# lab1_shkabara_usb_rs232.net
KiCad netlist of a schematic drawn in Altium Designer
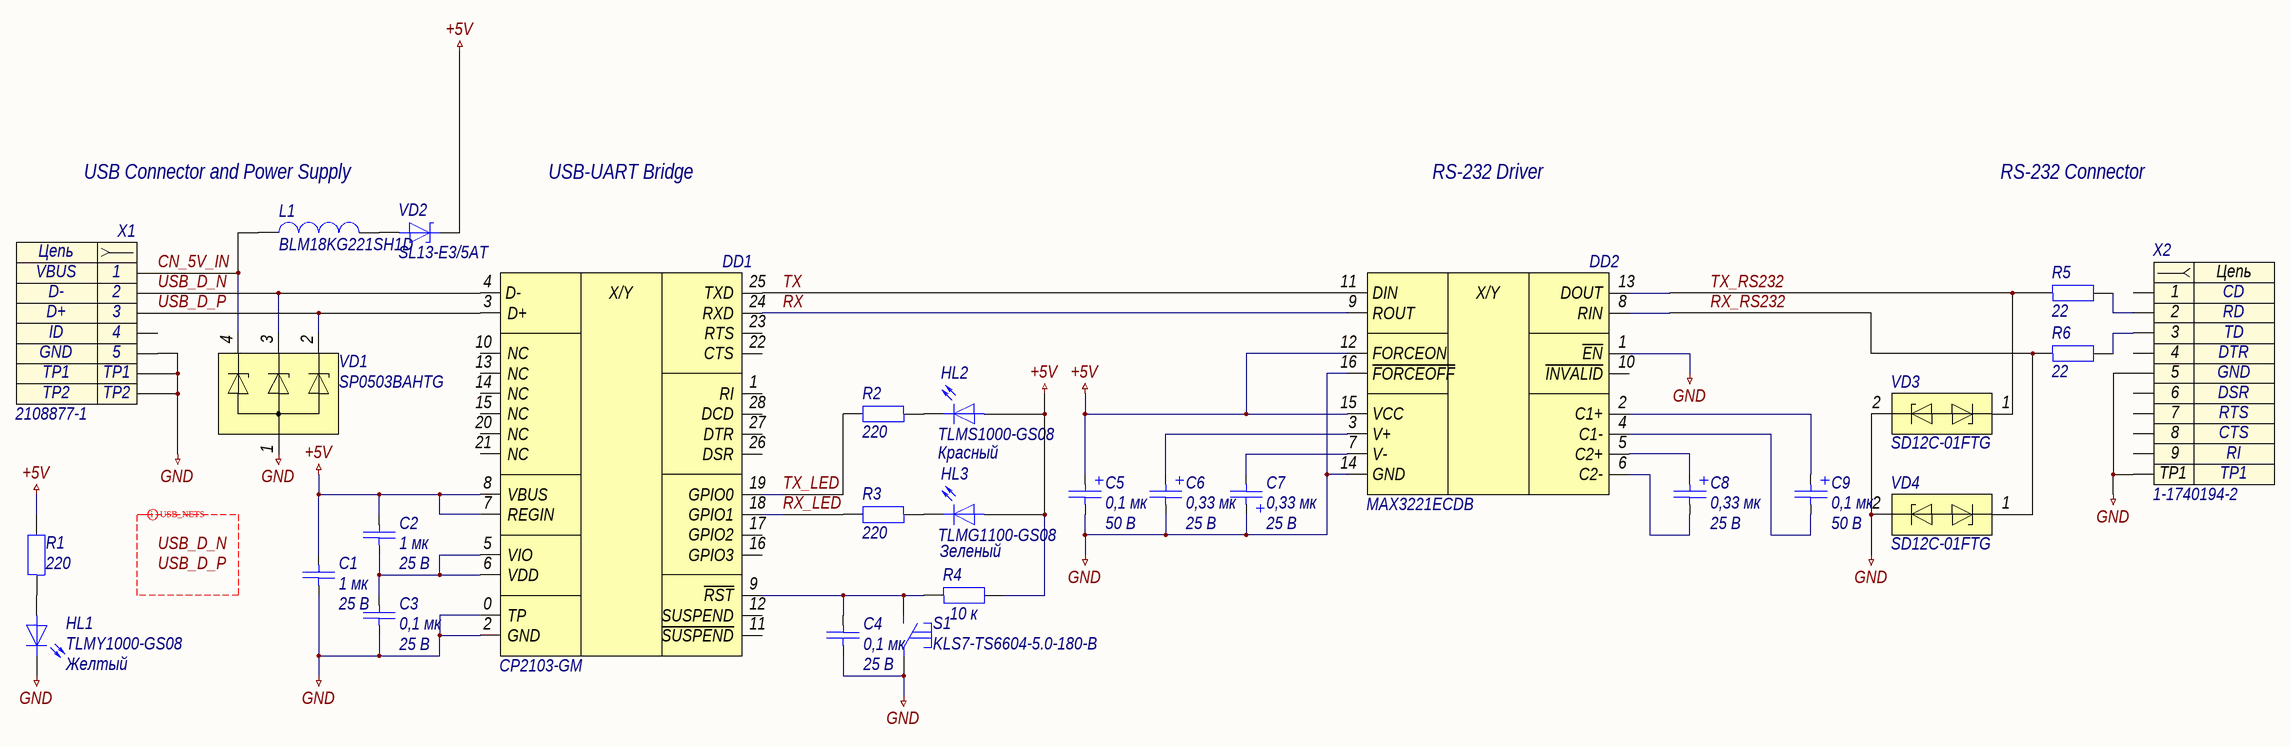
[diagram p0: lab1_shkabara_usb_rs232.SchDoc]

(export (version "E")
  (design (tool "Eeschema 10.0.6"))
  (components
    (comp (ref "C1")
      (value "1 мк")
      (footprint "C0603")
      (description "=Описание")
      (fields (field (name "НАПРЯЖЕНИЕ") "25 В"))
      (libsource (lib "Database_Students") (part "CAPACITOR-NONPOLAR"))
    )
    (comp (ref "C2")
      (value "1 мк")
      (footprint "C0603")
      (description "=Описание")
      (fields (field (name "НАПРЯЖЕНИЕ") "25 В"))
      (libsource (lib "Database_Students") (part "CAPACITOR-NONPOLAR"))
    )
    (comp (ref "C3")
      (value "0,1 мк")
      (footprint "C0603")
      (description "=Описание")
      (fields (field (name "НАПРЯЖЕНИЕ") "25 В"))
      (libsource (lib "Database_Students") (part "CAPACITOR-NONPOLAR"))
    )
    (comp (ref "C4")
      (value "0,1 мк")
      (footprint "C0603")
      (description "=Описание")
      (fields (field (name "НАПРЯЖЕНИЕ") "25 В"))
      (libsource (lib "Database_Students") (part "CAPACITOR-NONPOLAR"))
    )
    (comp (ref "C5")
      (value "0,1 мк")
      (footprint "C3216-18")
      (description "=Описание")
      (fields (field (name "НАПРЯЖЕНИЕ") "50 В"))
      (libsource (lib "Database_Students") (part "CAPACITOR-POLAR"))
    )
    (comp (ref "C6")
      (value "0,33 мк")
      (footprint "C3216-18")
      (description "=Описание")
      (fields (field (name "НАПРЯЖЕНИЕ") "25 В"))
      (libsource (lib "Database_Students") (part "CAPACITOR-POLAR"))
    )
    (comp (ref "C7")
      (value "0,33 мк")
      (footprint "C3216-18")
      (description "=Описание")
      (fields (field (name "НАПРЯЖЕНИЕ") "25 В"))
      (libsource (lib "Database_Students") (part "CAPACITOR-POLAR"))
    )
    (comp (ref "C8")
      (value "0,33 мк")
      (footprint "C3216-18")
      (description "=Описание")
      (fields (field (name "НАПРЯЖЕНИЕ") "25 В"))
      (libsource (lib "Database_Students") (part "CAPACITOR-POLAR"))
    )
    (comp (ref "C9")
      (value "0,1 мк")
      (footprint "C3216-18")
      (description "=Описание")
      (fields (field (name "НАПРЯЖЕНИЕ") "50 В"))
      (libsource (lib "Database_Students") (part "CAPACITOR-POLAR"))
    )
    (comp (ref "DD1")
      (value "CP2103-GM")
      (footprint "QFN-28-500X500X90")
      (description "=Описание")
      (libsource (lib "Database_Students") (part "CP2103-GM"))
    )
    (comp (ref "DD2")
      (value "MAX3221ECDB")
      (footprint "SSOP-16-620X530X195")
      (description "=Описание")
      (libsource (lib "Database_Students") (part "MAX3221ECDB"))
    )
    (comp (ref "HL1")
      (value "TLMY1000-GS08")
      (footprint "HL0603")
      (description "=Описание")
      (fields (field (name "ЦВЕТ") "Желтый"))
      (libsource (lib "Database_Students") (part "LED-COMMON"))
    )
    (comp (ref "HL2")
      (value "TLMS1000-GS08")
      (footprint "HL0603")
      (description "=Описание")
      (fields (field (name "ЦВЕТ") "Красный"))
      (libsource (lib "Database_Students") (part "LED-COMMON"))
    )
    (comp (ref "HL3")
      (value "TLMG1100-GS08")
      (footprint "HL0603")
      (description "=Описание")
      (fields (field (name "ЦВЕТ") "Зеленый"))
      (libsource (lib "Database_Students") (part "LED-COMMON"))
    )
    (comp (ref "L1")
      (value "BLM18KG221SH1D")
      (footprint "BLM-2-0603")
      (description "=Описание")
      (libsource (lib "Database_Students") (part "FERRITE-BEAD"))
    )
    (comp (ref "R1")
      (value "220")
      (footprint "R0603")
      (description "=Описание")
      (libsource (lib "Database_Students") (part "RESISTOR-COMMON"))
    )
    (comp (ref "R2")
      (value "220")
      (footprint "R0603")
      (description "=Описание")
      (libsource (lib "Database_Students") (part "RESISTOR-COMMON"))
    )
    (comp (ref "R3")
      (value "220")
      (footprint "R0603")
      (description "=Описание")
      (libsource (lib "Database_Students") (part "RESISTOR-COMMON"))
    )
    (comp (ref "R4")
      (value "10 к")
      (footprint "R0603")
      (description "=Описание")
      (libsource (lib "Database_Students") (part "RESISTOR-COMMON"))
    )
    (comp (ref "R5")
      (value "22")
      (footprint "R0603")
      (description "=Описание")
      (libsource (lib "Database_Students") (part "RESISTOR-COMMON"))
    )
    (comp (ref "R6")
      (value "22")
      (footprint "R0603")
      (description "=Описание")
      (libsource (lib "Database_Students") (part "RESISTOR-COMMON"))
    )
    (comp (ref "S1")
      (value "KLS7-TS6604-5.0-180-B")
      (footprint "KLS7-TS6604-5.0-180-B")
      (description "=Описание")
      (libsource (lib "Database_Students") (part "BUTTON"))
    )
    (comp (ref "VD1")
      (value "SP0503BAHTG")
      (footprint "SOT-143-4")
      (description "=Описание")
      (libsource (lib "Database_Students") (part "SP0503BAHTG"))
    )
    (comp (ref "VD2")
      (value "SL13-E3/5AT")
      (footprint "DO-214AC")
      (description "=Описание")
      (libsource (lib "Database_Students") (part "DIODE-SCHOTTKY"))
    )
    (comp (ref "VD3")
      (value "SD12C-01FTG")
      (footprint "SOD-323")
      (description "=Описание")
      (libsource (lib "Database_Students") (part "ZENER-BI-DIRECTIONAL"))
    )
    (comp (ref "VD4")
      (value "SD12C-01FTG")
      (footprint "SOD-323")
      (description "=Описание")
      (libsource (lib "Database_Students") (part "ZENER-BI-DIRECTIONAL"))
    )
    (comp (ref "X1")
      (value "2108877-1")
      (footprint "2108877-1")
      (libsource (lib "2108877-1_micro_usb-b") (part "2108877-1_micro_usb-b"))
    )
    (comp (ref "X2")
      (value "1-1740194-2")
      (footprint "Other:1-1740194-2")
      (description "D-Sub 9 pin Board-to-Board")
      (libsource (lib "Other") (part "HEADER-9-TP1-SCT"))
    )
  )
  (nets
    (net (code "1") (name "+5V") (class "Default")
      (node (ref "C1") (pin "1") (pinfunction "1_1") (pintype "passive"))
      (node (ref "C2") (pin "1") (pinfunction "1_1") (pintype "passive"))
      (node (ref "C5") (pin "1") (pinfunction "1_1") (pintype "passive"))
      (node (ref "DD1") (pin "7") (pinfunction "REGIN_7") (pintype "passive"))
      (node (ref "DD1") (pin "8") (pinfunction "VBUS_8") (pintype "passive"))
      (node (ref "DD2") (pin "12") (pinfunction "FORCEON_12") (pintype "passive"))
      (node (ref "DD2") (pin "15") (pinfunction "VCC_15") (pintype "passive"))
      (node (ref "HL2") (pin "2") (pinfunction "2_2") (pintype "passive"))
      (node (ref "HL3") (pin "2") (pinfunction "2_2") (pintype "passive"))
      (node (ref "R1") (pin "2") (pinfunction "2_2") (pintype "passive"))
      (node (ref "R4") (pin "2") (pinfunction "2_2") (pintype "passive"))
      (node (ref "VD2") (pin "1") (pinfunction "1_1") (pintype "passive"))
    )
    (net (code "2") (name "/CN_5V_IN") (class "Default")
      (node (ref "L1") (pin "1") (pinfunction "1_1") (pintype "passive"))
      (node (ref "VD1") (pin "4") (pinfunction "4_4") (pintype "passive"))
      (node (ref "X1") (pin "1") (pinfunction "1_1") (pintype "passive"))
    )
    (net (code "3") (name "/RX") (class "Default")
      (node (ref "DD1") (pin "24") (pinfunction "RXD_24") (pintype "passive"))
      (node (ref "DD2") (pin "9") (pinfunction "ROUT_9") (pintype "passive"))
    )
    (net (code "4") (name "/RX_LED") (class "Default")
      (node (ref "DD1") (pin "18") (pinfunction "GPIO1_18") (pintype "passive"))
      (node (ref "R3") (pin "2") (pinfunction "2_2") (pintype "passive"))
    )
    (net (code "5") (name "/RX_RS232") (class "Default")
      (node (ref "DD2") (pin "8") (pinfunction "RIN_8") (pintype "passive"))
      (node (ref "R6") (pin "1") (pinfunction "1_1") (pintype "passive"))
      (node (ref "VD4") (pin "1") (pinfunction "1_1") (pintype "passive"))
    )
    (net (code "6") (name "/TX") (class "Default")
      (node (ref "DD1") (pin "25") (pinfunction "TXD_25") (pintype "passive"))
      (node (ref "DD2") (pin "11") (pinfunction "DIN_11") (pintype "passive"))
    )
    (net (code "7") (name "/TX_LED") (class "Default")
      (node (ref "DD1") (pin "19") (pinfunction "GPIO0_19") (pintype "passive"))
      (node (ref "R2") (pin "2") (pinfunction "2_2") (pintype "passive"))
    )
    (net (code "8") (name "/TX_RS232") (class "Default")
      (node (ref "DD2") (pin "13") (pinfunction "DOUT_13") (pintype "passive"))
      (node (ref "R5") (pin "1") (pinfunction "1_1") (pintype "passive"))
      (node (ref "VD3") (pin "1") (pinfunction "1_1") (pintype "passive"))
    )
    (net (code "9") (name "/USB_D_N") (class "Default")
      (node (ref "DD1") (pin "4") (pinfunction "D-_4") (pintype "passive"))
      (node (ref "VD1") (pin "3") (pinfunction "3_3") (pintype "passive"))
      (node (ref "X1") (pin "2") (pinfunction "2_2") (pintype "passive"))
    )
    (net (code "10") (name "/USB_D_P") (class "Default")
      (node (ref "DD1") (pin "3") (pinfunction "D+_3") (pintype "passive"))
      (node (ref "VD1") (pin "2") (pinfunction "2_2") (pintype "passive"))
      (node (ref "X1") (pin "3") (pinfunction "3_3") (pintype "passive"))
    )
    (net (code "11") (name "GND") (class "Default")
      (node (ref "C1") (pin "2") (pinfunction "2_2") (pintype "passive"))
      (node (ref "C3") (pin "2") (pinfunction "2_2") (pintype "passive"))
      (node (ref "C4") (pin "1") (pinfunction "1_1") (pintype "passive"))
      (node (ref "C5") (pin "2") (pinfunction "2_2") (pintype "passive"))
      (node (ref "C6") (pin "2") (pinfunction "2_2") (pintype "passive"))
      (node (ref "C7") (pin "1") (pinfunction "1_1") (pintype "passive"))
      (node (ref "DD1") (pin "0") (pinfunction "TP_0") (pintype "passive"))
      (node (ref "DD1") (pin "2") (pinfunction "GND_2") (pintype "passive"))
      (node (ref "DD2") (pin "1") (pinfunction "~{EN}_1") (pintype "passive"))
      (node (ref "DD2") (pin "14") (pinfunction "GND_14") (pintype "passive"))
      (node (ref "DD2") (pin "16") (pinfunction "~{FORCEOFF}_16") (pintype "passive"))
      (node (ref "HL1") (pin "1") (pinfunction "1_1") (pintype "passive"))
      (node (ref "S1") (pin "1") (pinfunction "1_1") (pintype "passive"))
      (node (ref "VD1") (pin "1") (pinfunction "1_1") (pintype "passive"))
      (node (ref "VD3") (pin "2") (pinfunction "2_2") (pintype "passive"))
      (node (ref "VD4") (pin "2") (pinfunction "2_2") (pintype "passive"))
      (node (ref "X1") (pin "5") (pinfunction "5_5") (pintype "passive"))
      (node (ref "X1") (pin "TP1") (pinfunction "TP1_TP1") (pintype "passive"))
      (node (ref "X1") (pin "TP2") (pinfunction "TP2_TP2") (pintype "passive"))
      (node (ref "X2") (pin "5") (pinfunction "5_5") (pintype "passive"))
      (node (ref "X2") (pin "TP1") (pinfunction "TP1_TP1") (pintype "passive"))
    )
    (net (code "12") (name "Net-(DD1-VDD)") (class "Default")
      (node (ref "C2") (pin "2") (pinfunction "2_2") (pintype "passive"))
      (node (ref "C3") (pin "1") (pinfunction "1_1") (pintype "passive"))
      (node (ref "DD1") (pin "5") (pinfunction "VIO_5") (pintype "passive"))
      (node (ref "DD1") (pin "6") (pinfunction "VDD_6") (pintype "passive"))
    )
    (net (code "13") (name "Net-(DD1-~{RST})") (class "Default")
      (node (ref "C4") (pin "2") (pinfunction "2_2") (pintype "passive"))
      (node (ref "DD1") (pin "9") (pinfunction "~{RST}_9") (pintype "passive"))
      (node (ref "R4") (pin "1") (pinfunction "1_1") (pintype "passive"))
      (node (ref "S1") (pin "2") (pinfunction "2_2") (pintype "passive"))
    )
    (net (code "14") (name "Net-(DD2-C1+)") (class "Default")
      (node (ref "C9") (pin "1") (pinfunction "1_1") (pintype "passive"))
      (node (ref "DD2") (pin "2") (pinfunction "C1+_2") (pintype "passive"))
    )
    (net (code "15") (name "Net-(DD2-C1-)") (class "Default")
      (node (ref "C9") (pin "2") (pinfunction "2_2") (pintype "passive"))
      (node (ref "DD2") (pin "4") (pinfunction "C1-_4") (pintype "passive"))
    )
    (net (code "16") (name "Net-(DD2-C2+)") (class "Default")
      (node (ref "C8") (pin "1") (pinfunction "1_1") (pintype "passive"))
      (node (ref "DD2") (pin "5") (pinfunction "C2+_5") (pintype "passive"))
    )
    (net (code "17") (name "Net-(DD2-C2-)") (class "Default")
      (node (ref "C8") (pin "2") (pinfunction "2_2") (pintype "passive"))
      (node (ref "DD2") (pin "6") (pinfunction "C2-_6") (pintype "passive"))
    )
    (net (code "18") (name "Net-(DD2-V+)") (class "Default")
      (node (ref "C6") (pin "1") (pinfunction "1_1") (pintype "passive"))
      (node (ref "DD2") (pin "3") (pinfunction "V+_3") (pintype "passive"))
    )
    (net (code "19") (name "Net-(DD2-V-)") (class "Default")
      (node (ref "C7") (pin "2") (pinfunction "2_2") (pintype "passive"))
      (node (ref "DD2") (pin "7") (pinfunction "V-_7") (pintype "passive"))
    )
    (net (code "20") (name "Net-(HL1-Pad2)") (class "Default")
      (node (ref "HL1") (pin "2") (pinfunction "2_2") (pintype "passive"))
      (node (ref "R1") (pin "1") (pinfunction "1_1") (pintype "passive"))
    )
    (net (code "21") (name "Net-(HL2-Pad1)") (class "Default")
      (node (ref "HL2") (pin "1") (pinfunction "1_1") (pintype "passive"))
      (node (ref "R2") (pin "1") (pinfunction "1_1") (pintype "passive"))
    )
    (net (code "22") (name "Net-(HL3-Pad1)") (class "Default")
      (node (ref "HL3") (pin "1") (pinfunction "1_1") (pintype "passive"))
      (node (ref "R3") (pin "1") (pinfunction "1_1") (pintype "passive"))
    )
    (net (code "23") (name "Net-(L1-Pad2)") (class "Default")
      (node (ref "L1") (pin "2") (pinfunction "2_2") (pintype "passive"))
      (node (ref "VD2") (pin "2") (pinfunction "2_2") (pintype "passive"))
    )
    (net (code "24") (name "Net-(R5-Pad2)") (class "Default")
      (node (ref "R5") (pin "2") (pinfunction "2_2") (pintype "passive"))
      (node (ref "X2") (pin "2") (pinfunction "2_2") (pintype "passive"))
    )
    (net (code "25") (name "Net-(R6-Pad2)") (class "Default")
      (node (ref "R6") (pin "2") (pinfunction "2_2") (pintype "passive"))
      (node (ref "X2") (pin "3") (pinfunction "3_3") (pintype "passive"))
    )
    (net (code "26") (name "unconnected-(DD1-CTS-Pad22)") (class "Default")
      (node (ref "DD1") (pin "22") (pinfunction "CTS_22") (pintype "passive"))
    )
    (net (code "27") (name "unconnected-(DD1-DCD-Pad28)") (class "Default")
      (node (ref "DD1") (pin "28") (pinfunction "DCD_28") (pintype "passive"))
    )
    (net (code "28") (name "unconnected-(DD1-DSR-Pad26)") (class "Default")
      (node (ref "DD1") (pin "26") (pinfunction "DSR_26") (pintype "passive"))
    )
    (net (code "29") (name "unconnected-(DD1-DTR-Pad27)") (class "Default")
      (node (ref "DD1") (pin "27") (pinfunction "DTR_27") (pintype "passive"))
    )
    (net (code "30") (name "unconnected-(DD1-GPIO2-Pad17)") (class "Default")
      (node (ref "DD1") (pin "17") (pinfunction "GPIO2_17") (pintype "passive"))
    )
    (net (code "31") (name "unconnected-(DD1-GPIO3-Pad16)") (class "Default")
      (node (ref "DD1") (pin "16") (pinfunction "GPIO3_16") (pintype "passive"))
    )
    (net (code "32") (name "unconnected-(DD1-NC-Pad10)") (class "Default")
      (node (ref "DD1") (pin "10") (pinfunction "NC_10") (pintype "passive"))
    )
    (net (code "33") (name "unconnected-(DD1-NC-Pad13)") (class "Default")
      (node (ref "DD1") (pin "13") (pinfunction "NC_13") (pintype "passive"))
    )
    (net (code "34") (name "unconnected-(DD1-NC-Pad14)") (class "Default")
      (node (ref "DD1") (pin "14") (pinfunction "NC_14") (pintype "passive"))
    )
    (net (code "35") (name "unconnected-(DD1-NC-Pad15)") (class "Default")
      (node (ref "DD1") (pin "15") (pinfunction "NC_15") (pintype "passive"))
    )
    (net (code "36") (name "unconnected-(DD1-NC-Pad20)") (class "Default")
      (node (ref "DD1") (pin "20") (pinfunction "NC_20") (pintype "passive"))
    )
    (net (code "37") (name "unconnected-(DD1-NC-Pad21)") (class "Default")
      (node (ref "DD1") (pin "21") (pinfunction "NC_21") (pintype "passive"))
    )
    (net (code "38") (name "unconnected-(DD1-RI-Pad1)") (class "Default")
      (node (ref "DD1") (pin "1") (pinfunction "RI_1") (pintype "passive"))
    )
    (net (code "39") (name "unconnected-(DD1-RTS-Pad23)") (class "Default")
      (node (ref "DD1") (pin "23") (pinfunction "RTS_23") (pintype "passive"))
    )
    (net (code "40") (name "unconnected-(DD1-SUSPEND-Pad12)") (class "Default")
      (node (ref "DD1") (pin "12") (pinfunction "SUSPEND_12") (pintype "passive"))
    )
    (net (code "41") (name "unconnected-(DD1-~{SUSPEND}-Pad11)") (class "Default")
      (node (ref "DD1") (pin "11") (pinfunction "~{SUSPEND}_11") (pintype "passive"))
    )
    (net (code "42") (name "unconnected-(DD2-~{INVALID}-Pad10)") (class "Default")
      (node (ref "DD2") (pin "10") (pinfunction "~{INVALID}_10") (pintype "passive"))
    )
    (net (code "43") (name "unconnected-(X1-Pad4)") (class "Default")
      (node (ref "X1") (pin "4") (pinfunction "4_4") (pintype "passive"))
    )
    (net (code "44") (name "unconnected-(X2-Pad1)") (class "Default")
      (node (ref "X2") (pin "1") (pinfunction "1_1") (pintype "passive"))
    )
    (net (code "45") (name "unconnected-(X2-Pad4)") (class "Default")
      (node (ref "X2") (pin "4") (pinfunction "4_4") (pintype "passive"))
    )
    (net (code "46") (name "unconnected-(X2-Pad6)") (class "Default")
      (node (ref "X2") (pin "6") (pinfunction "6_6") (pintype "passive"))
    )
    (net (code "47") (name "unconnected-(X2-Pad7)") (class "Default")
      (node (ref "X2") (pin "7") (pinfunction "7_7") (pintype "passive"))
    )
    (net (code "48") (name "unconnected-(X2-Pad8)") (class "Default")
      (node (ref "X2") (pin "8") (pinfunction "8_8") (pintype "passive"))
    )
    (net (code "49") (name "unconnected-(X2-Pad9)") (class "Default")
      (node (ref "X2") (pin "9") (pinfunction "9_9") (pintype "passive"))
    )
  )
)
